# receiver-d.net
KiCad netlist of a schematic drawn in Altium Designer
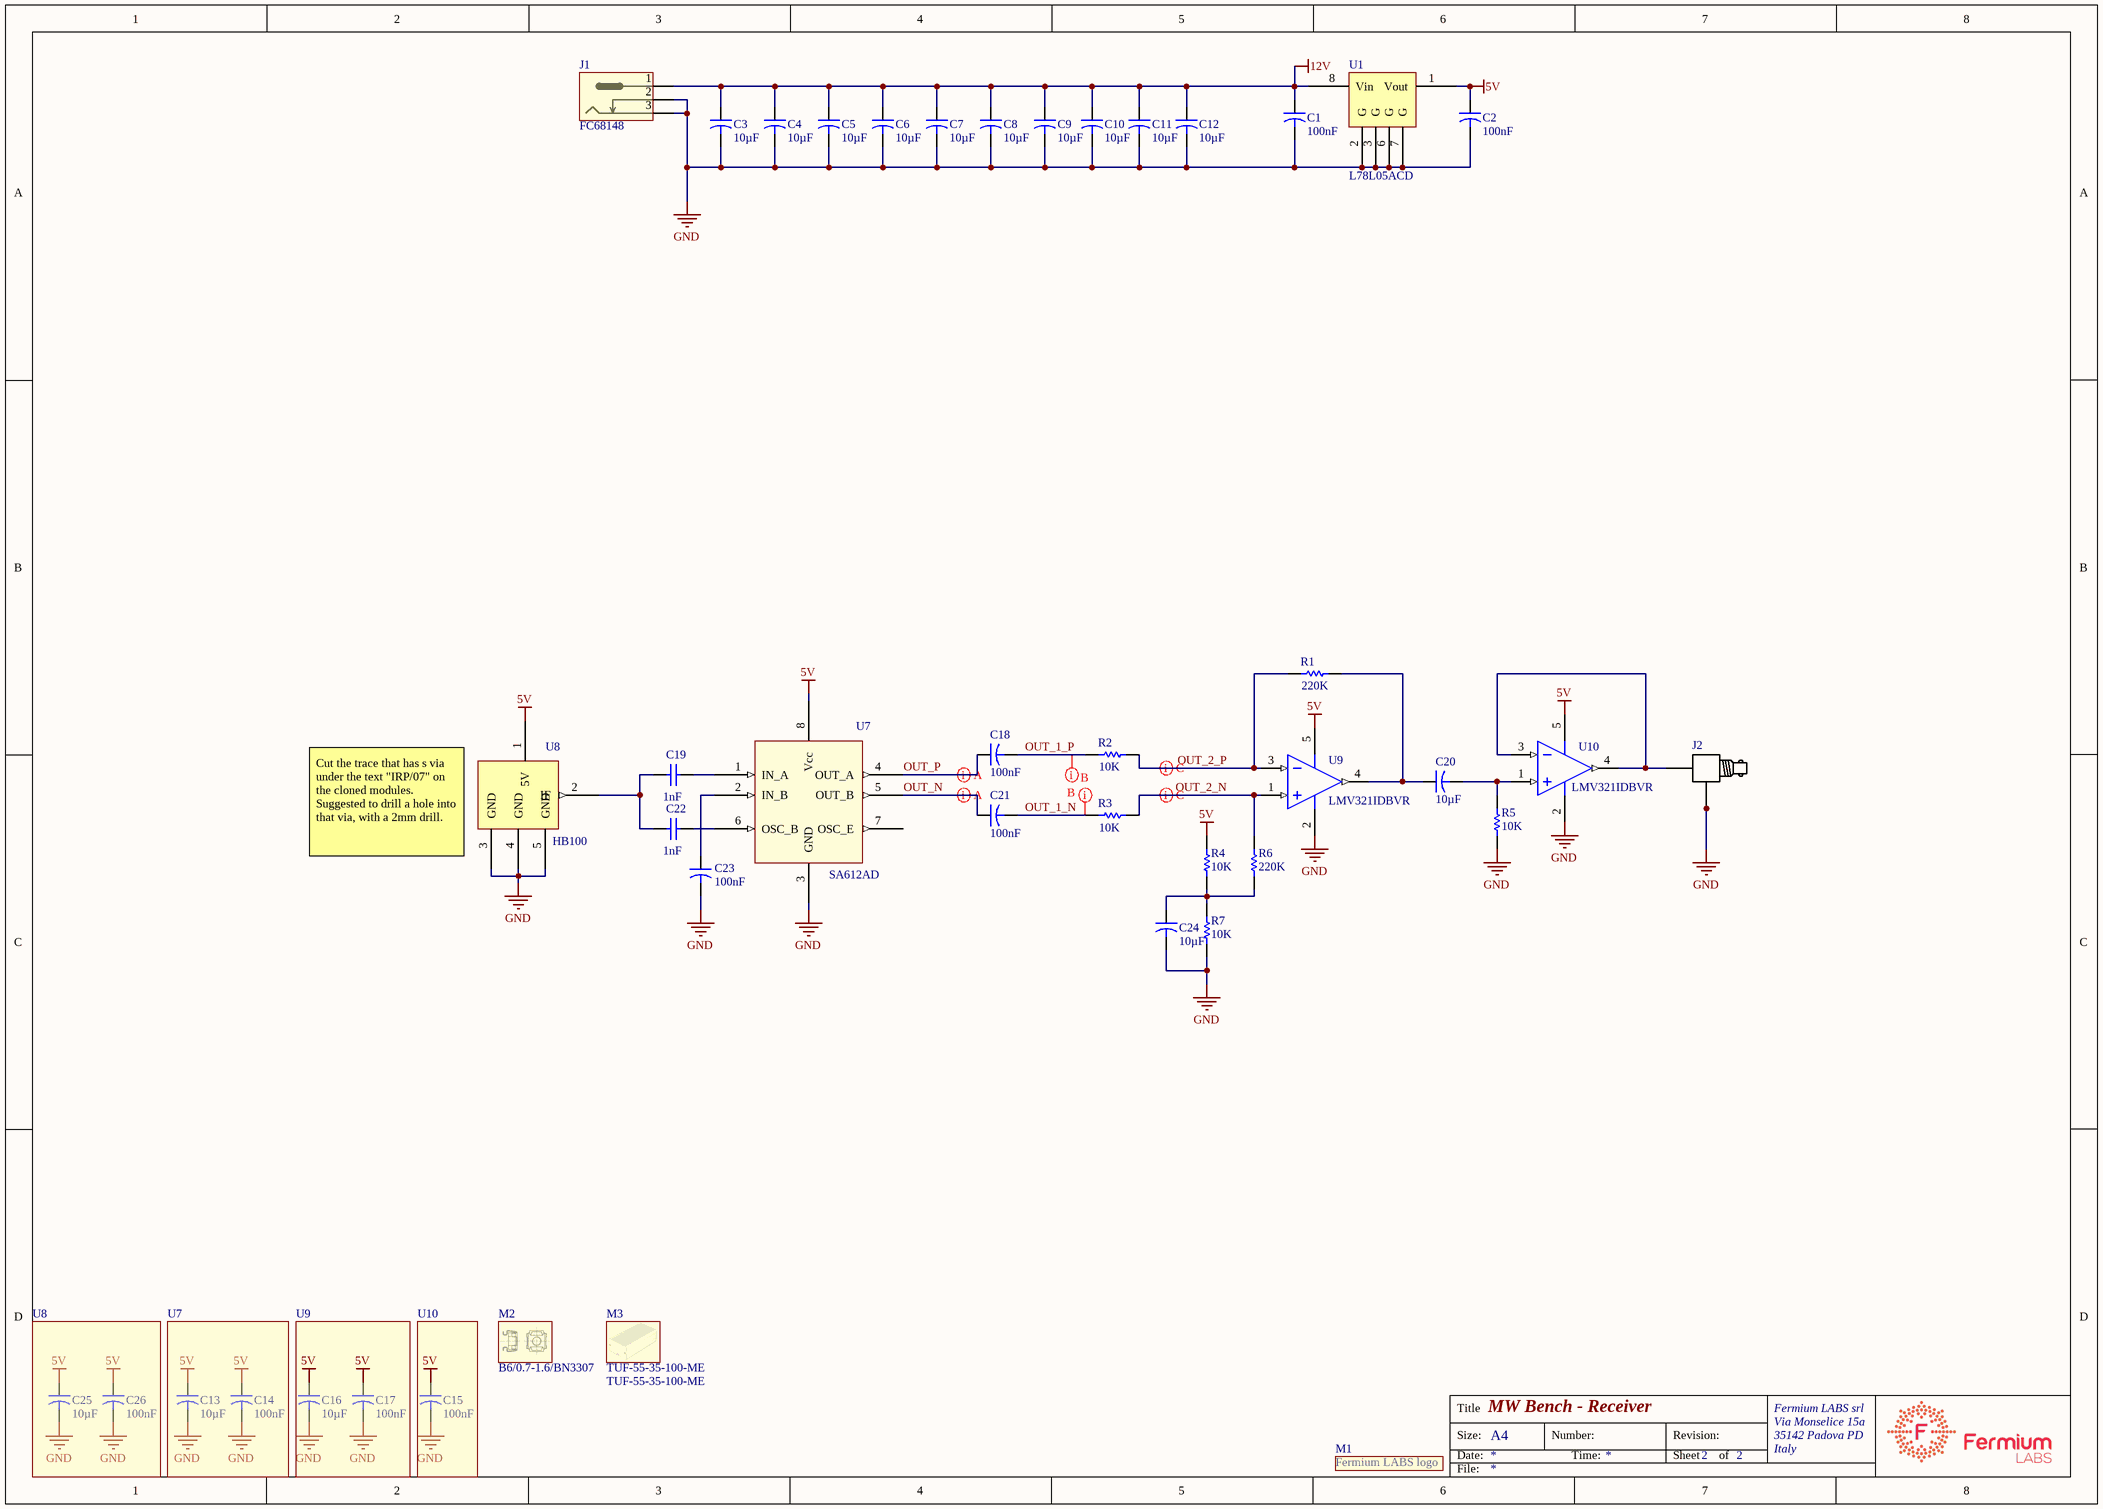
[diagram p0: receiver-d.SchDoc]

(export (version "E")
  (design (tool "Eeschema 10.0.6"))
  (components
    (comp (ref "C1")
      (value "~")
      (footprint "Passives:CAP 0805/2012")
      (description "Capacitor")
      (fields
        (field (name "CAPACITANCE") "100nF")
        (field (name "MANUFACTURER") "YAGEO")
        (field (name "MANUFACTURER PART NUMBER") "CC0805JRX7R9BB104")
      )
      (libsource (lib "Miscellaneous Devices") (part "Cap2"))
    )
    (comp (ref "C2")
      (value "~")
      (footprint "Passives:CAP 0805/2012")
      (description "Capacitor")
      (fields
        (field (name "CAPACITANCE") "100nF")
        (field (name "MANUFACTURER") "YAGEO")
        (field (name "MANUFACTURER PART NUMBER") "CC0805JRX7R9BB104")
      )
      (libsource (lib "Miscellaneous Devices") (part "Cap2"))
    )
    (comp (ref "C3")
      (value "~")
      (footprint "Passives:CAP 1206/3216")
      (description "Capacitor")
      (fields
        (field (name "MANUFACTURER") "SAMSUNG")
        (field (name "MANUFACTURER PART NUMBER") "CL31A106KAHNNNE")
        (field (name "CAPACITANCE") "10µF")
        (field (name "PUBLISHER") "Altium Limited")
      )
      (libsource (lib "Miscellaneous Devices") (part "Cap2"))
    )
    (comp (ref "C4")
      (value "~")
      (footprint "Passives:CAP 1206/3216")
      (description "Capacitor")
      (fields
        (field (name "MANUFACTURER") "SAMSUNG")
        (field (name "MANUFACTURER PART NUMBER") "CL31A106KAHNNNE")
        (field (name "CAPACITANCE") "10µF")
        (field (name "PUBLISHER") "Altium Limited")
      )
      (libsource (lib "Miscellaneous Devices") (part "Cap2"))
    )
    (comp (ref "C5")
      (value "~")
      (footprint "Passives:CAP 1206/3216")
      (description "Capacitor")
      (fields
        (field (name "MANUFACTURER") "SAMSUNG")
        (field (name "MANUFACTURER PART NUMBER") "CL31A106KAHNNNE")
        (field (name "CAPACITANCE") "10µF")
        (field (name "PUBLISHER") "Altium Limited")
      )
      (libsource (lib "Miscellaneous Devices") (part "Cap2"))
    )
    (comp (ref "C6")
      (value "~")
      (footprint "Passives:CAP 1206/3216")
      (description "Capacitor")
      (fields
        (field (name "MANUFACTURER") "SAMSUNG")
        (field (name "MANUFACTURER PART NUMBER") "CL31A106KAHNNNE")
        (field (name "CAPACITANCE") "10µF")
        (field (name "PUBLISHER") "Altium Limited")
      )
      (libsource (lib "Miscellaneous Devices") (part "Cap2"))
    )
    (comp (ref "C7")
      (value "~")
      (footprint "Passives:CAP 1206/3216")
      (description "Capacitor")
      (fields
        (field (name "MANUFACTURER") "SAMSUNG")
        (field (name "MANUFACTURER PART NUMBER") "CL31A106KAHNNNE")
        (field (name "CAPACITANCE") "10µF")
        (field (name "PUBLISHER") "Altium Limited")
      )
      (libsource (lib "Miscellaneous Devices") (part "Cap2"))
    )
    (comp (ref "C8")
      (value "~")
      (footprint "Passives:CAP 1206/3216")
      (description "Capacitor")
      (fields
        (field (name "MANUFACTURER") "SAMSUNG")
        (field (name "MANUFACTURER PART NUMBER") "CL31A106KAHNNNE")
        (field (name "CAPACITANCE") "10µF")
        (field (name "PUBLISHER") "Altium Limited")
      )
      (libsource (lib "Miscellaneous Devices") (part "Cap2"))
    )
    (comp (ref "C9")
      (value "~")
      (footprint "Passives:CAP 1206/3216")
      (description "Capacitor")
      (fields
        (field (name "MANUFACTURER") "SAMSUNG")
        (field (name "MANUFACTURER PART NUMBER") "CL31A106KAHNNNE")
        (field (name "CAPACITANCE") "10µF")
        (field (name "PUBLISHER") "Altium Limited")
      )
      (libsource (lib "Miscellaneous Devices") (part "Cap2"))
    )
    (comp (ref "C10")
      (value "~")
      (footprint "Passives:CAP 1206/3216")
      (description "Capacitor")
      (fields
        (field (name "MANUFACTURER") "SAMSUNG")
        (field (name "MANUFACTURER PART NUMBER") "CL31A106KAHNNNE")
        (field (name "CAPACITANCE") "10µF")
        (field (name "PUBLISHER") "Altium Limited")
      )
      (libsource (lib "Miscellaneous Devices") (part "Cap2"))
    )
    (comp (ref "C11")
      (value "~")
      (footprint "Passives:CAP 1206/3216")
      (description "Capacitor")
      (fields
        (field (name "MANUFACTURER") "SAMSUNG")
        (field (name "MANUFACTURER PART NUMBER") "CL31A106KAHNNNE")
        (field (name "CAPACITANCE") "10µF")
        (field (name "PUBLISHER") "Altium Limited")
      )
      (libsource (lib "Miscellaneous Devices") (part "Cap2"))
    )
    (comp (ref "C12")
      (value "~")
      (footprint "Passives:CAP 1206/3216")
      (description "Capacitor")
      (fields
        (field (name "MANUFACTURER") "SAMSUNG")
        (field (name "MANUFACTURER PART NUMBER") "CL31A106KAHNNNE")
        (field (name "CAPACITANCE") "10µF")
        (field (name "PUBLISHER") "Altium Limited")
      )
      (libsource (lib "Miscellaneous Devices") (part "Cap2"))
    )
    (comp (ref "C13")
      (value "~")
      (footprint "Passives:CAP 1206/3216")
      (description "Capacitor")
      (fields
        (field (name "MANUFACTURER") "SAMSUNG")
        (field (name "MANUFACTURER PART NUMBER") "CL31A106KAHNNNE")
        (field (name "CAPACITANCE") "10µF")
        (field (name "PUBLISHER") "Altium Limited")
      )
      (libsource (lib "Miscellaneous Devices") (part "Cap2"))
    )
    (comp (ref "C14")
      (value "~")
      (footprint "Passives:CAP 0805/2012")
      (description "Capacitor")
      (fields
        (field (name "CAPACITANCE") "100nF")
        (field (name "MANUFACTURER") "YAGEO")
        (field (name "MANUFACTURER PART NUMBER") "CC0805JRX7R9BB104")
      )
      (libsource (lib "Miscellaneous Devices") (part "Cap2"))
    )
    (comp (ref "C15")
      (value "~")
      (footprint "Passives:CAP 0805/2012")
      (description "Capacitor")
      (fields
        (field (name "CAPACITANCE") "100nF")
        (field (name "MANUFACTURER") "YAGEO")
        (field (name "MANUFACTURER PART NUMBER") "CC0805JRX7R9BB104")
      )
      (libsource (lib "Miscellaneous Devices") (part "Cap2"))
    )
    (comp (ref "C16")
      (value "~")
      (footprint "Passives:CAP 1206/3216")
      (description "Capacitor")
      (fields
        (field (name "MANUFACTURER") "SAMSUNG")
        (field (name "MANUFACTURER PART NUMBER") "CL31A106KAHNNNE")
        (field (name "CAPACITANCE") "10µF")
        (field (name "PUBLISHER") "Altium Limited")
      )
      (libsource (lib "Miscellaneous Devices") (part "Cap2"))
    )
    (comp (ref "C17")
      (value "~")
      (footprint "Passives:CAP 0805/2012")
      (description "Capacitor")
      (fields
        (field (name "CAPACITANCE") "100nF")
        (field (name "MANUFACTURER") "YAGEO")
        (field (name "MANUFACTURER PART NUMBER") "CC0805JRX7R9BB104")
      )
      (libsource (lib "Miscellaneous Devices") (part "Cap2"))
    )
    (comp (ref "C18")
      (value "~")
      (footprint "Passives:CAP 0805/2012")
      (description "Capacitor")
      (fields
        (field (name "CAPACITANCE") "100nF")
        (field (name "MANUFACTURER") "YAGEO")
        (field (name "MANUFACTURER PART NUMBER") "CC0805JRX7R9BB104")
      )
      (libsource (lib "Miscellaneous Devices") (part "Cap2"))
    )
    (comp (ref "C19")
      (value "1nF")
      (footprint "CAP 0805/2012")
      (description "Capacitor")
      (fields
        (field (name "MANUFACTURER") "Samsung")
        (field (name "MANUFACTURER PART NUMBER") "CL21B102KCANNNC")
      )
      (libsource (lib "Miscellaneous Devices") (part "Cap"))
    )
    (comp (ref "C20")
      (value "~")
      (footprint "Passives:CAP 1206/3216")
      (description "Capacitor")
      (fields
        (field (name "MANUFACTURER") "SAMSUNG")
        (field (name "MANUFACTURER PART NUMBER") "CL31A106KAHNNNE")
        (field (name "CAPACITANCE") "10µF")
        (field (name "PUBLISHER") "Altium Limited")
      )
      (libsource (lib "Miscellaneous Devices") (part "Cap2"))
    )
    (comp (ref "C21")
      (value "~")
      (footprint "Passives:CAP 0805/2012")
      (description "Capacitor")
      (fields
        (field (name "CAPACITANCE") "100nF")
        (field (name "MANUFACTURER") "YAGEO")
        (field (name "MANUFACTURER PART NUMBER") "CC0805JRX7R9BB104")
      )
      (libsource (lib "Miscellaneous Devices") (part "Cap2"))
    )
    (comp (ref "C22")
      (value "1nF")
      (footprint "CAP 0805/2012")
      (description "Capacitor")
      (fields
        (field (name "MANUFACTURER") "Samsung")
        (field (name "MANUFACTURER PART NUMBER") "CL21B102KCANNNC")
      )
      (libsource (lib "Miscellaneous Devices") (part "Cap"))
    )
    (comp (ref "C23")
      (value "~")
      (footprint "Passives:CAP 0805/2012")
      (description "Capacitor")
      (fields
        (field (name "CAPACITANCE") "100nF")
        (field (name "MANUFACTURER") "YAGEO")
        (field (name "MANUFACTURER PART NUMBER") "CC0805JRX7R9BB104")
      )
      (libsource (lib "Miscellaneous Devices") (part "Cap2"))
    )
    (comp (ref "C24")
      (value "~")
      (footprint "Passives:CAP 1206/3216")
      (description "Capacitor")
      (fields
        (field (name "MANUFACTURER") "SAMSUNG")
        (field (name "MANUFACTURER PART NUMBER") "CL31A106KAHNNNE")
        (field (name "CAPACITANCE") "10µF")
        (field (name "PUBLISHER") "Altium Limited")
      )
      (libsource (lib "Miscellaneous Devices") (part "Cap2"))
    )
    (comp (ref "C25")
      (value "~")
      (footprint "Passives:CAP 1206/3216")
      (description "Capacitor")
      (fields
        (field (name "MANUFACTURER") "SAMSUNG")
        (field (name "MANUFACTURER PART NUMBER") "CL31A106KAHNNNE")
        (field (name "CAPACITANCE") "10µF")
        (field (name "PUBLISHER") "Altium Limited")
      )
      (libsource (lib "Miscellaneous Devices") (part "Cap2"))
    )
    (comp (ref "C26")
      (value "~")
      (footprint "Passives:CAP 0805/2012")
      (description "Capacitor")
      (fields
        (field (name "CAPACITANCE") "100nF")
        (field (name "MANUFACTURER") "YAGEO")
        (field (name "MANUFACTURER PART NUMBER") "CC0805JRX7R9BB104")
      )
      (libsource (lib "Miscellaneous Devices") (part "Cap2"))
    )
    (comp (ref "J1")
      (value "~")
      (footprint "custom_components:dc-jack")
      (fields
        (field (name "SUPPLIER PART NUMBER 1") "FC68148")
        (field (name "MANUFACTURER") "CLIFF")
        (field (name "MANUFACTURER PART NUMBER") "DC-10A FC68148")
      )
      (libsource (lib "custom_components") (part "jackdc"))
    )
    (comp (ref "J2")
      (value "~")
      (footprint "BNC-RA")
      (description "connector bnc")
      (fields
        (field (name "MANUFACTURER") "TE CONNECTIVITY")
        (field (name "MANUFACTURER PART NUMBER") "1-1337543-0")
      )
      (libsource (lib "TH Connectors") (part "BNC-PCB-RA"))
    )
    (comp (ref "M1")
      (value "fermiumlabs-logo")
      (footprint "frm-med")
      (libsource (lib "custom_components") (part "fermiumlabs-logo"))
    )
    (comp (ref "M2")
      (value "B6/0.7-1.6/BN3307")
      (fields (field (name "SUPPLIER PART NUMBER 1") "B6/0.7-1.6/BN3307"))
      (libsource (lib "custom_components_ltk_mw") (part "B6/0.7-1.6/BN3307"))
    )
    (comp (ref "M3")
      (value "TUF-55-35-100-ME")
      (fields (field (name "SUPPLIER PART NUMBER 1") "TUF-55-35-100-ME"))
      (libsource (lib "custom_components_ltk_mw") (part "TUF-55-35-100-ME"))
    )
    (comp (ref "R1")
      (value "220K")
      (footprint "RES 0805/2012")
      (description "Resistor")
      (fields
        (field (name "MANUFACTURER") "Royal Electronic Factory")
        (field (name "MANUFACTURER PART NUMBER") "0805S8J0224T5E")
      )
      (libsource (lib "Miscellaneous Devices") (part "Res1"))
    )
    (comp (ref "R2")
      (value "10K")
      (footprint "RES 0805/2012")
      (description "Resistor")
      (fields
        (field (name "MANUFACTURER") "Royal Electronic Factory")
        (field (name "MANUFACTURER PART NUMBER") "0805S8J0103T5E")
      )
      (libsource (lib "Miscellaneous Devices") (part "Res1"))
    )
    (comp (ref "R3")
      (value "10K")
      (footprint "RES 0805/2012")
      (description "Resistor")
      (fields
        (field (name "MANUFACTURER") "Royal Electronic Factory")
        (field (name "MANUFACTURER PART NUMBER") "0805S8J0103T5E")
      )
      (libsource (lib "Miscellaneous Devices") (part "Res1"))
    )
    (comp (ref "R4")
      (value "10K")
      (footprint "RES 0805/2012")
      (description "Resistor")
      (fields
        (field (name "MANUFACTURER") "Royal Electronic Factory")
        (field (name "MANUFACTURER PART NUMBER") "0805S8J0103T5E")
      )
      (libsource (lib "Miscellaneous Devices") (part "Res1"))
    )
    (comp (ref "R5")
      (value "10K")
      (footprint "RES 0805/2012")
      (description "Resistor")
      (fields
        (field (name "MANUFACTURER") "Royal Electronic Factory")
        (field (name "MANUFACTURER PART NUMBER") "0805S8J0103T5E")
      )
      (libsource (lib "Miscellaneous Devices") (part "Res1"))
    )
    (comp (ref "R6")
      (value "220K")
      (footprint "RES 0805/2012")
      (description "Resistor")
      (fields
        (field (name "MANUFACTURER") "Royal Electronic Factory")
        (field (name "MANUFACTURER PART NUMBER") "0805S8J0224T5E")
      )
      (libsource (lib "Miscellaneous Devices") (part "Res1"))
    )
    (comp (ref "R7")
      (value "10K")
      (footprint "RES 0805/2012")
      (description "Resistor")
      (fields
        (field (name "MANUFACTURER") "Royal Electronic Factory")
        (field (name "MANUFACTURER PART NUMBER") "0805S8J0103T5E")
      )
      (libsource (lib "Miscellaneous Devices") (part "Res1"))
    )
    (comp (ref "U1")
      (value "L78L05ACD")
      (footprint "ST SOIC-8N")
      (fields (field (name "SUPPLIER PART NUMBER 1") "L78L05ACD"))
      (libsource (lib "custom_components_ltk_mw") (part "L78L05ACD"))
    )
    (comp (ref "U7")
      (value "SA612A")
      (footprint "TI SOIC-8 D")
      (fields (field (name "SUPPLIER PART NUMBER 1") "SA612AD"))
      (libsource (lib "custom_components_ltk_mw") (part "SA612A"))
    )
    (comp (ref "U8")
      (value "HB100")
      (footprint "HB100-buried")
      (fields (field (name "MANUFACTURER") "China unspecified"))
      (libsource (lib "custom_components_ltk_mw") (part "HB100"))
    )
    (comp (ref "U9")
      (value "U*")
      (footprint "TI SOT-23-5 DBV")
      (fields (field (name "SUPPLIER PART NUMBER 1") "LMV321IDBVR"))
      (libsource (lib "custom_components_ltk_mw") (part "LMV321IDBVR"))
    )
    (comp (ref "U10")
      (value "U*")
      (footprint "TI SOT-23-5 DBV")
      (fields (field (name "SUPPLIER PART NUMBER 1") "LMV321IDBVR"))
      (libsource (lib "custom_components_ltk_mw") (part "LMV321IDBVR"))
    )
  )
  (nets
    (net (code "1") (name "/OUT_1_N") (class "Default")
      (node (ref "C21") (pin "2") (pinfunction "2_2") (pintype "passive"))
      (node (ref "R3") (pin "1") (pinfunction "1_1") (pintype "passive"))
    )
    (net (code "2") (name "/OUT_1_P") (class "Default")
      (node (ref "C18") (pin "2") (pinfunction "2_2") (pintype "passive"))
      (node (ref "R2") (pin "1") (pinfunction "1_1") (pintype "passive"))
    )
    (net (code "3") (name "/OUT_2_N") (class "Default")
      (node (ref "R3") (pin "2") (pinfunction "2_2") (pintype "passive"))
      (node (ref "R6") (pin "2") (pinfunction "2_2") (pintype "passive"))
      (node (ref "U9") (pin "1") (pinfunction "IN+_1") (pintype "input"))
    )
    (net (code "4") (name "/OUT_2_P") (class "Default")
      (node (ref "R1") (pin "1") (pinfunction "1_1") (pintype "passive"))
      (node (ref "R2") (pin "2") (pinfunction "2_2") (pintype "passive"))
      (node (ref "U9") (pin "3") (pinfunction "IN-_3") (pintype "input"))
    )
    (net (code "5") (name "/OUT_N") (class "Default")
      (node (ref "C21") (pin "1") (pinfunction "1_1") (pintype "passive"))
      (node (ref "U7") (pin "5") (pinfunction "OUT_B_5") (pintype "output"))
    )
    (net (code "6") (name "/OUT_P") (class "Default")
      (node (ref "C18") (pin "1") (pinfunction "1_1") (pintype "passive"))
      (node (ref "U7") (pin "4") (pinfunction "OUT_A_4") (pintype "output"))
    )
    (net (code "7") (name "5V") (class "Default")
      (node (ref "C13") (pin "1") (pinfunction "1_1") (pintype "passive"))
      (node (ref "C14") (pin "1") (pinfunction "1_1") (pintype "passive"))
      (node (ref "C15") (pin "1") (pinfunction "1_1") (pintype "passive"))
      (node (ref "C16") (pin "1") (pinfunction "1_1") (pintype "passive"))
      (node (ref "C17") (pin "1") (pinfunction "1_1") (pintype "passive"))
      (node (ref "C2") (pin "1") (pinfunction "1_1") (pintype "passive"))
      (node (ref "C25") (pin "1") (pinfunction "1_1") (pintype "passive"))
      (node (ref "C26") (pin "1") (pinfunction "1_1") (pintype "passive"))
      (node (ref "R4") (pin "2") (pinfunction "2_2") (pintype "passive"))
      (node (ref "U1") (pin "1") (pinfunction "Vout_1") (pintype "power_in"))
      (node (ref "U10") (pin "5") (pinfunction "VDD+_5") (pintype "power_in"))
      (node (ref "U7") (pin "8") (pinfunction "Vcc_8") (pintype "power_in"))
      (node (ref "U8") (pin "1") (pinfunction "5V_1") (pintype "power_in"))
      (node (ref "U9") (pin "5") (pinfunction "VDD+_5") (pintype "power_in"))
    )
    (net (code "8") (name "12V") (class "Default")
      (node (ref "C1") (pin "1") (pinfunction "1_1") (pintype "passive"))
      (node (ref "C10") (pin "1") (pinfunction "1_1") (pintype "passive"))
      (node (ref "C11") (pin "1") (pinfunction "1_1") (pintype "passive"))
      (node (ref "C12") (pin "1") (pinfunction "1_1") (pintype "passive"))
      (node (ref "C3") (pin "1") (pinfunction "1_1") (pintype "passive"))
      (node (ref "C4") (pin "1") (pinfunction "1_1") (pintype "passive"))
      (node (ref "C5") (pin "1") (pinfunction "1_1") (pintype "passive"))
      (node (ref "C6") (pin "1") (pinfunction "1_1") (pintype "passive"))
      (node (ref "C7") (pin "1") (pinfunction "1_1") (pintype "passive"))
      (node (ref "C8") (pin "1") (pinfunction "1_1") (pintype "passive"))
      (node (ref "C9") (pin "1") (pinfunction "1_1") (pintype "passive"))
      (node (ref "J1") (pin "1") (pinfunction "1_1") (pintype "passive"))
      (node (ref "U1") (pin "8") (pinfunction "Vin_8") (pintype "power_in"))
    )
    (net (code "9") (name "GND") (class "Default")
      (node (ref "C1") (pin "2") (pinfunction "2_2") (pintype "passive"))
      (node (ref "C10") (pin "2") (pinfunction "2_2") (pintype "passive"))
      (node (ref "C11") (pin "2") (pinfunction "2_2") (pintype "passive"))
      (node (ref "C12") (pin "2") (pinfunction "2_2") (pintype "passive"))
      (node (ref "C13") (pin "2") (pinfunction "2_2") (pintype "passive"))
      (node (ref "C14") (pin "2") (pinfunction "2_2") (pintype "passive"))
      (node (ref "C15") (pin "2") (pinfunction "2_2") (pintype "passive"))
      (node (ref "C16") (pin "2") (pinfunction "2_2") (pintype "passive"))
      (node (ref "C17") (pin "2") (pinfunction "2_2") (pintype "passive"))
      (node (ref "C2") (pin "2") (pinfunction "2_2") (pintype "passive"))
      (node (ref "C23") (pin "2") (pinfunction "2_2") (pintype "passive"))
      (node (ref "C24") (pin "2") (pinfunction "2_2") (pintype "passive"))
      (node (ref "C25") (pin "2") (pinfunction "2_2") (pintype "passive"))
      (node (ref "C26") (pin "2") (pinfunction "2_2") (pintype "passive"))
      (node (ref "C3") (pin "2") (pinfunction "2_2") (pintype "passive"))
      (node (ref "C4") (pin "2") (pinfunction "2_2") (pintype "passive"))
      (node (ref "C5") (pin "2") (pinfunction "2_2") (pintype "passive"))
      (node (ref "C6") (pin "2") (pinfunction "2_2") (pintype "passive"))
      (node (ref "C7") (pin "2") (pinfunction "2_2") (pintype "passive"))
      (node (ref "C8") (pin "2") (pinfunction "2_2") (pintype "passive"))
      (node (ref "C9") (pin "2") (pinfunction "2_2") (pintype "passive"))
      (node (ref "J1") (pin "2") (pinfunction "2_2") (pintype "passive"))
      (node (ref "J1") (pin "3") (pinfunction "3_3") (pintype "passive"))
      (node (ref "J2") (pin "2") (pinfunction "gnd_2") (pintype "passive"))
      (node (ref "J2") (pin "A") (pinfunction "A_A") (pintype "passive"))
      (node (ref "J2") (pin "B") (pinfunction "B_B") (pintype "passive"))
      (node (ref "R5") (pin "1") (pinfunction "1_1") (pintype "passive"))
      (node (ref "R7") (pin "1") (pinfunction "1_1") (pintype "passive"))
      (node (ref "U1") (pin "2") (pinfunction "G_2") (pintype "power_in"))
      (node (ref "U1") (pin "3") (pinfunction "G_3") (pintype "power_in"))
      (node (ref "U1") (pin "6") (pinfunction "G_6") (pintype "power_in"))
      (node (ref "U1") (pin "7") (pinfunction "G_7") (pintype "power_in"))
      (node (ref "U10") (pin "2") (pinfunction "VDD-_2") (pintype "power_in"))
      (node (ref "U7") (pin "3") (pinfunction "GND_3") (pintype "power_in"))
      (node (ref "U8") (pin "3") (pinfunction "GND_3") (pintype "power_in"))
      (node (ref "U8") (pin "4") (pinfunction "GND_4") (pintype "power_in"))
      (node (ref "U8") (pin "5") (pinfunction "GND_5") (pintype "power_in"))
      (node (ref "U9") (pin "2") (pinfunction "VDD-_2") (pintype "power_in"))
    )
    (net (code "10") (name "Net-(C24-Pad1)") (class "Default")
      (node (ref "C24") (pin "1") (pinfunction "1_1") (pintype "passive"))
      (node (ref "R4") (pin "1") (pinfunction "1_1") (pintype "passive"))
      (node (ref "R6") (pin "1") (pinfunction "1_1") (pintype "passive"))
      (node (ref "R7") (pin "2") (pinfunction "2_2") (pintype "passive"))
    )
    (net (code "11") (name "Net-(U7-IN_A)") (class "Default")
      (node (ref "C19") (pin "2") (pinfunction "2_2") (pintype "passive"))
      (node (ref "U7") (pin "1") (pinfunction "IN_A_1") (pintype "input"))
    )
    (net (code "12") (name "Net-(U7-IN_B)") (class "Default")
      (node (ref "C23") (pin "1") (pinfunction "1_1") (pintype "passive"))
      (node (ref "U7") (pin "2") (pinfunction "IN_B_2") (pintype "input"))
    )
    (net (code "13") (name "Net-(U7-OSC_B)") (class "Default")
      (node (ref "C22") (pin "2") (pinfunction "2_2") (pintype "passive"))
      (node (ref "U7") (pin "6") (pinfunction "OSC_B_6") (pintype "input"))
    )
    (net (code "14") (name "Net-(U8-IF)") (class "Default")
      (node (ref "C19") (pin "1") (pinfunction "1_1") (pintype "passive"))
      (node (ref "C22") (pin "1") (pinfunction "1_1") (pintype "passive"))
      (node (ref "U8") (pin "2") (pinfunction "IF_2") (pintype "output"))
    )
    (net (code "15") (name "Net-(U9-OUT)") (class "Default")
      (node (ref "C20") (pin "1") (pinfunction "1_1") (pintype "passive"))
      (node (ref "R1") (pin "2") (pinfunction "2_2") (pintype "passive"))
      (node (ref "U9") (pin "4") (pinfunction "OUT_4") (pintype "output"))
    )
    (net (code "16") (name "Net-(U10-IN+)") (class "Default")
      (node (ref "C20") (pin "2") (pinfunction "2_2") (pintype "passive"))
      (node (ref "R5") (pin "2") (pinfunction "2_2") (pintype "passive"))
      (node (ref "U10") (pin "1") (pinfunction "IN+_1") (pintype "input"))
    )
    (net (code "17") (name "Net-(U10-IN-)") (class "Default")
      (node (ref "J2") (pin "1") (pinfunction "1_1") (pintype "passive"))
      (node (ref "U10") (pin "3") (pinfunction "IN-_3") (pintype "input"))
      (node (ref "U10") (pin "4") (pinfunction "OUT_4") (pintype "output"))
    )
    (net (code "18") (name "unconnected-(U7-OSC_E-Pad7)") (class "Default")
      (node (ref "U7") (pin "7") (pinfunction "OSC_E_7") (pintype "output"))
    )
  )
)
